# MCU.net
KiCad netlist of a schematic drawn in Altium Designer
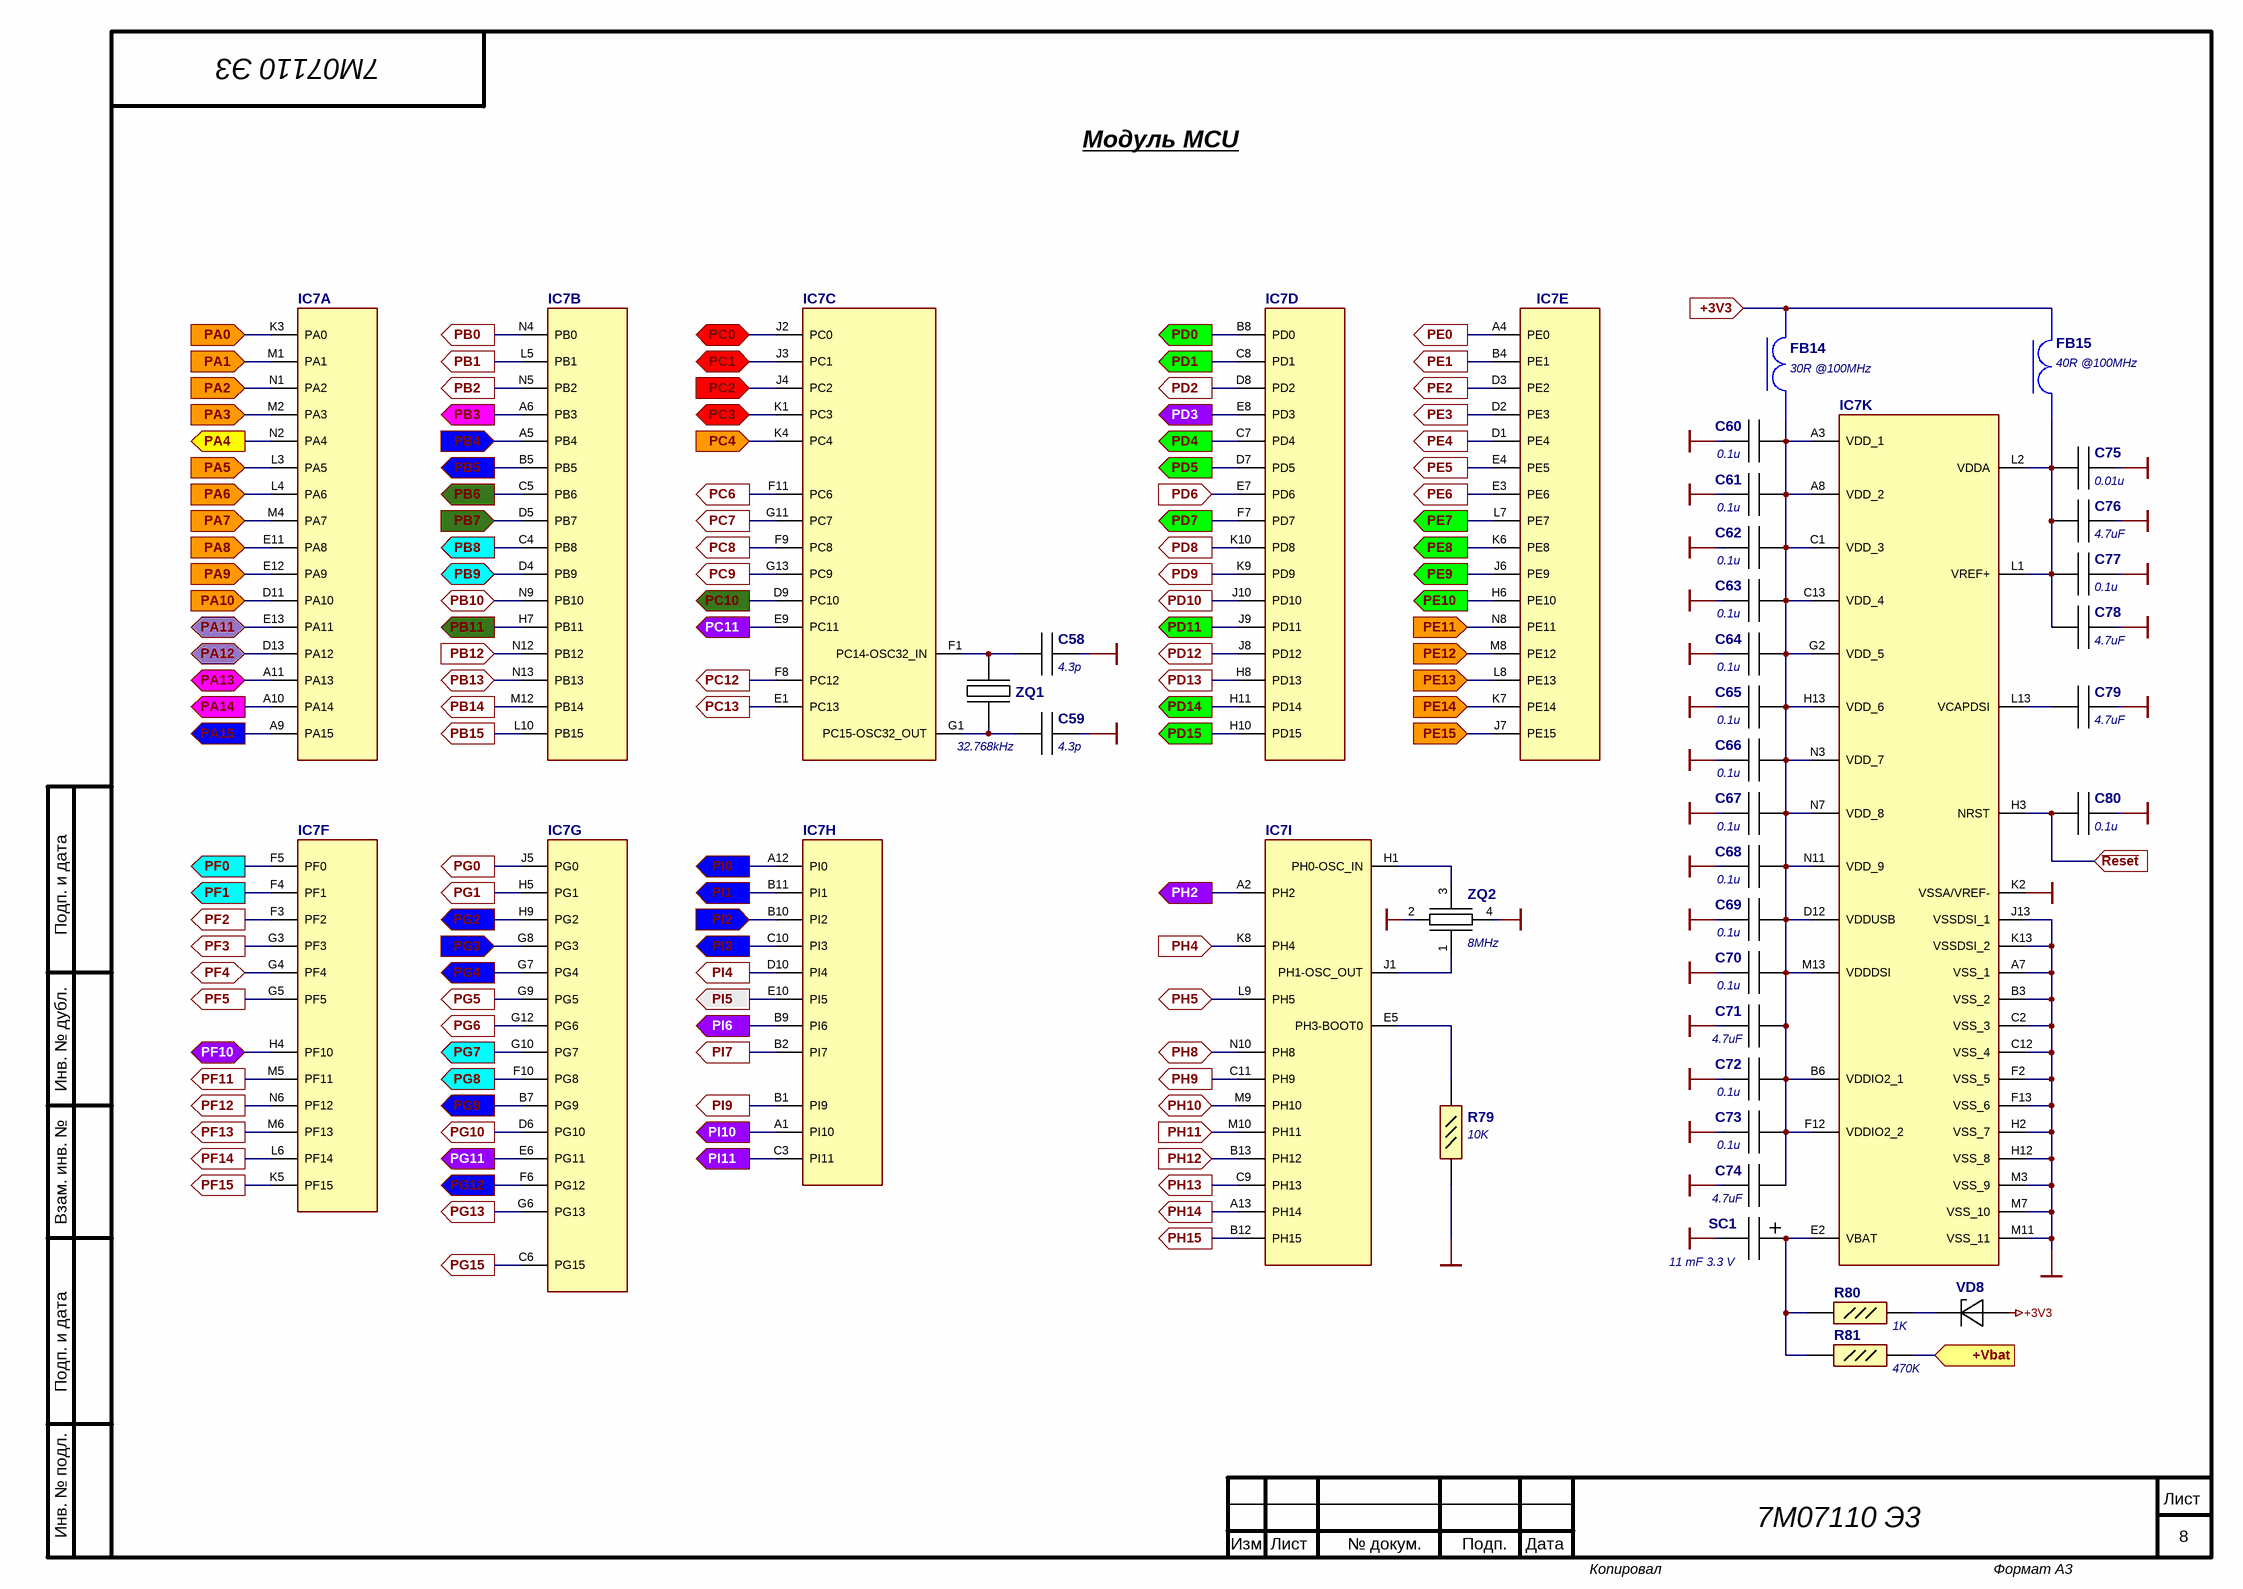
[diagram p0: Модуль MCU.SchDoc]

(export (version "E")
  (design (tool "Eeschema 10.0.6"))
  (components
    (comp (ref "C58")
      (value "4.3p")
      (footprint ":CAP0402 100x50x50")
      (description "CAP CER  50V C0G/NP0 0402")
      (fields (field (name "MANUFACTURER_PART_NUMBER") "GJM1555C1H4R3CB01D"))
      (libsource (lib "Capacitors 0402") (part "GJM1555C1H4R3CB01D"))
    )
    (comp (ref "C59")
      (value "4.3p")
      (footprint ":CAP0402 100x50x50")
      (description "CAP CER  50V C0G/NP0 0402")
      (fields (field (name "MANUFACTURER_PART_NUMBER") "GJM1555C1H4R3CB01D"))
      (libsource (lib "Capacitors 0402") (part "GJM1555C1H4R3CB01D"))
    )
    (comp (ref "C60")
      (value "0.1u")
      (footprint ":CAP0402 100x50x50")
      (description "±10% 25V Ceramic Capacitor X7R 0402 (1005 Metric)")
      (fields
        (field (name "MANUFACTURER_PART_NUMBER") "GRM155R71E104KE14J")
        (field (name "MOUSER PART NUMBER") "81-GRM155R71E104KE4J")
      )
      (libsource (lib "Capacitors 0402") (part "GRM155R71E104KE14J"))
    )
    (comp (ref "C61")
      (value "0.1u")
      (footprint ":CAP0402 100x50x50")
      (description "±10% 25V Ceramic Capacitor X7R 0402 (1005 Metric)")
      (fields
        (field (name "MANUFACTURER_PART_NUMBER") "GRM155R71E104KE14J")
        (field (name "MOUSER PART NUMBER") "81-GRM155R71E104KE4J")
      )
      (libsource (lib "Capacitors 0402") (part "GRM155R71E104KE14J"))
    )
    (comp (ref "C62")
      (value "0.1u")
      (footprint ":CAP0402 100x50x50")
      (description "±10% 25V Ceramic Capacitor X7R 0402 (1005 Metric)")
      (fields
        (field (name "MANUFACTURER_PART_NUMBER") "GRM155R71E104KE14J")
        (field (name "MOUSER PART NUMBER") "81-GRM155R71E104KE4J")
      )
      (libsource (lib "Capacitors 0402") (part "GRM155R71E104KE14J"))
    )
    (comp (ref "C63")
      (value "0.1u")
      (footprint ":CAP0402 100x50x50")
      (description "±10% 25V Ceramic Capacitor X7R 0402 (1005 Metric)")
      (fields
        (field (name "MANUFACTURER_PART_NUMBER") "GRM155R71E104KE14J")
        (field (name "MOUSER PART NUMBER") "81-GRM155R71E104KE4J")
      )
      (libsource (lib "Capacitors 0402") (part "GRM155R71E104KE14J"))
    )
    (comp (ref "C64")
      (value "0.1u")
      (footprint ":CAP0402 100x50x50")
      (description "±10% 25V Ceramic Capacitor X7R 0402 (1005 Metric)")
      (fields
        (field (name "MANUFACTURER_PART_NUMBER") "GRM155R71E104KE14J")
        (field (name "MOUSER PART NUMBER") "81-GRM155R71E104KE4J")
      )
      (libsource (lib "Capacitors 0402") (part "GRM155R71E104KE14J"))
    )
    (comp (ref "C65")
      (value "0.1u")
      (footprint ":CAP0402 100x50x50")
      (description "±10% 25V Ceramic Capacitor X7R 0402 (1005 Metric)")
      (fields
        (field (name "MANUFACTURER_PART_NUMBER") "GRM155R71E104KE14J")
        (field (name "MOUSER PART NUMBER") "81-GRM155R71E104KE4J")
      )
      (libsource (lib "Capacitors 0402") (part "GRM155R71E104KE14J"))
    )
    (comp (ref "C66")
      (value "0.1u")
      (footprint ":CAP0402 100x50x50")
      (description "±10% 25V Ceramic Capacitor X7R 0402 (1005 Metric)")
      (fields
        (field (name "MANUFACTURER_PART_NUMBER") "GRM155R71E104KE14J")
        (field (name "MOUSER PART NUMBER") "81-GRM155R71E104KE4J")
      )
      (libsource (lib "Capacitors 0402") (part "GRM155R71E104KE14J"))
    )
    (comp (ref "C67")
      (value "0.1u")
      (footprint ":CAP0402 100x50x50")
      (description "±10% 25V Ceramic Capacitor X7R 0402 (1005 Metric)")
      (fields
        (field (name "MANUFACTURER_PART_NUMBER") "GRM155R71E104KE14J")
        (field (name "MOUSER PART NUMBER") "81-GRM155R71E104KE4J")
      )
      (libsource (lib "Capacitors 0402") (part "GRM155R71E104KE14J"))
    )
    (comp (ref "C68")
      (value "0.1u")
      (footprint ":CAP0402 100x50x50")
      (description "±10% 25V Ceramic Capacitor X7R 0402 (1005 Metric)")
      (fields
        (field (name "MANUFACTURER_PART_NUMBER") "GRM155R71E104KE14J")
        (field (name "MOUSER PART NUMBER") "81-GRM155R71E104KE4J")
      )
      (libsource (lib "Capacitors 0402") (part "GRM155R71E104KE14J"))
    )
    (comp (ref "C69")
      (value "0.1u")
      (footprint ":CAP0402 100x50x50")
      (description "±10% 25V Ceramic Capacitor X7R 0402 (1005 Metric)")
      (fields
        (field (name "MANUFACTURER_PART_NUMBER") "GRM155R71E104KE14J")
        (field (name "MOUSER PART NUMBER") "81-GRM155R71E104KE4J")
      )
      (libsource (lib "Capacitors 0402") (part "GRM155R71E104KE14J"))
    )
    (comp (ref "C70")
      (value "0.1u")
      (footprint ":CAP0402 100x50x50")
      (description "±10% 25V Ceramic Capacitor X7R 0402 (1005 Metric)")
      (fields
        (field (name "MANUFACTURER_PART_NUMBER") "GRM155R71E104KE14J")
        (field (name "MOUSER PART NUMBER") "81-GRM155R71E104KE4J")
      )
      (libsource (lib "Capacitors 0402") (part "GRM155R71E104KE14J"))
    )
    (comp (ref "C71")
      (value "4.7uF")
      (footprint ":CAP0805 C2012X125")
      (description "CAP CER 4.7uF 25V X7R 0805")
      (fields (field (name "MANUFACTURER_PART_NUMBER") "GRM21BZ71E475KE15L"))
      (libsource (lib "Capacitors 0805") (part "GRM21BZ71E475KE15L"))
    )
    (comp (ref "C72")
      (value "0.1u")
      (footprint ":CAP0402 100x50x50")
      (description "±10% 25V Ceramic Capacitor X7R 0402 (1005 Metric)")
      (fields
        (field (name "MANUFACTURER_PART_NUMBER") "GRM155R71E104KE14J")
        (field (name "MOUSER PART NUMBER") "81-GRM155R71E104KE4J")
      )
      (libsource (lib "Capacitors 0402") (part "GRM155R71E104KE14J"))
    )
    (comp (ref "C73")
      (value "0.1u")
      (footprint ":CAP0402 100x50x50")
      (description "±10% 25V Ceramic Capacitor X7R 0402 (1005 Metric)")
      (fields
        (field (name "MANUFACTURER_PART_NUMBER") "GRM155R71E104KE14J")
        (field (name "MOUSER PART NUMBER") "81-GRM155R71E104KE4J")
      )
      (libsource (lib "Capacitors 0402") (part "GRM155R71E104KE14J"))
    )
    (comp (ref "C74")
      (value "4.7uF")
      (footprint ":CAP0805 C2012X125")
      (description "CAP CER 4.7uF 25V X7R 0805")
      (fields (field (name "MANUFACTURER_PART_NUMBER") "GRM21BZ71E475KE15L"))
      (libsource (lib "Capacitors 0805") (part "GRM21BZ71E475KE15L"))
    )
    (comp (ref "C75")
      (value "0.01u")
      (footprint ":CAP0402 100x50x50")
      (description "±5% 35V Ceramic Capacitor C0G, NP0 0402 (1005 Metric)")
      (fields (field (name "MANUFACTURER_PART_NUMBER") "GRM1555CYA103JE01D"))
      (libsource (lib "Capacitors 0402") (part "GRM1555CYA103JE01D"))
    )
    (comp (ref "C76")
      (value "4.7uF")
      (footprint ":CAP0805 C2012X125")
      (description "CAP CER 4.7uF 25V X7R 0805")
      (fields (field (name "MANUFACTURER_PART_NUMBER") "GRM21BZ71E475KE15L"))
      (libsource (lib "Capacitors 0805") (part "GRM21BZ71E475KE15L"))
    )
    (comp (ref "C77")
      (value "0.1u")
      (footprint ":CAP0402 100x50x50")
      (description "±10% 25V Ceramic Capacitor X7R 0402 (1005 Metric)")
      (fields
        (field (name "MANUFACTURER_PART_NUMBER") "GRM155R71E104KE14J")
        (field (name "MOUSER PART NUMBER") "81-GRM155R71E104KE4J")
      )
      (libsource (lib "Capacitors 0402") (part "GRM155R71E104KE14J"))
    )
    (comp (ref "C78")
      (value "4.7uF")
      (footprint ":CAP0805 C2012X125")
      (description "CAP CER 4.7uF 25V X7R 0805")
      (fields (field (name "MANUFACTURER_PART_NUMBER") "GRM21BZ71E475KE15L"))
      (libsource (lib "Capacitors 0805") (part "GRM21BZ71E475KE15L"))
    )
    (comp (ref "C79")
      (value "4.7uF")
      (footprint ":CAP0805 C2012X125")
      (description "CAP CER 4.7uF 25V X7R 0805")
      (fields (field (name "MANUFACTURER_PART_NUMBER") "GRM21BZ71E475KE15L"))
      (libsource (lib "Capacitors 0805") (part "GRM21BZ71E475KE15L"))
    )
    (comp (ref "C80")
      (value "0.1u")
      (footprint ":CAP0402 100x50x50")
      (description "±10% 25V Ceramic Capacitor X7R 0402 (1005 Metric)")
      (fields
        (field (name "MANUFACTURER_PART_NUMBER") "GRM155R71E104KE14J")
        (field (name "MOUSER PART NUMBER") "81-GRM155R71E104KE4J")
      )
      (libsource (lib "Capacitors 0402") (part "GRM155R71E104KE14J"))
    )
    (comp (ref "FB14")
      (value "30R @100MHz")
      (footprint ":FER BLM18SP300SN1D")
      (description "30 Ohms @ 100MHz 1 Power Line Ferrite Bead 0603 (1608 Metric) 6A 8mOhm")
      (fields
        (field (name "MANUFACTURER_PART_NUMBER") "BLM18SP300SN1D")
        (field (name "MOUSER PART NUMBER") "81-BLM18SP300SN1D")
      )
      (libsource (lib "Ferrite Bead") (part "BLM18SP300SN1D"))
    )
    (comp (ref "FB15")
      (value "40R @100MHz")
      (footprint ":FER MMZ1005Y400CTD25")
      (description "40 Ohms @ 100MHz 1 Signal Line Ferrite Bead 0402 (1005 Metric) 550mA 100mOhm")
      (fields
        (field (name "MANUFACTURER_PART_NUMBER") "MMZ1005Y400CTD25")
        (field (name "MOUSER PART NUMBER") "810-MMZ1005Y400CTD25")
      )
      (libsource (lib "Ferrite Bead") (part "MMZ1005Y400CTD25"))
    )
    (comp (ref "IC7")
      (value "STM32L4S9AII6")
      (footprint ":BGA169 P700X700X60")
      (description "MCU 32BIT 2MB FLASH")
      (fields (field (name "MOUSER PART NUMBER") "511-STM32L4S9AII6"))
      (libsource (lib "") (part "STM32L4S9AII6_1"))
    )
    (comp (ref "R79")
      (value "RC0402FR-07")
      (footprint ":RES0402")
      (fields (field (name "MANUFACTURER_PART_NUMBER (PART 2: VALUE)") "10K"))
      (libsource (lib "") (part "RC0402FR-07_1"))
    )
    (comp (ref "R80")
      (value "RC0402FR-07")
      (footprint ":RES0402")
      (fields (field (name "MANUFACTURER_PART_NUMBER (PART 2: VALUE)") "1K"))
      (libsource (lib "Resistors 0402") (part "RC0402FR-07"))
    )
    (comp (ref "R81")
      (value "RC0402FR-07")
      (footprint ":RES0402")
      (fields (field (name "MANUFACTURER_PART_NUMBER (PART 2: VALUE)") "470K"))
      (libsource (lib "Resistors 0402") (part "RC0402FR-07"))
    )
    (comp (ref "SC1")
      (value "11 mF 3.3 V")
      (footprint ":CAP CPH3225A")
      (description "11 mF (EDLC) Supercapacitor 3.3 V 1210 (3225 Metric)")
      (fields
        (field (name "MANUFACTURER_PART_NUMBER") "CPH3225A")
        (field (name "MOUSER PART NUMBER") "628-CPH3225A")
      )
      (libsource (lib "Super Capacitors") (part "CPH3225A"))
    )
    (comp (ref "VD8")
      (value "30V 0.1A")
      (footprint ":DIODE SOD-923F")
      (description "Diodes Schottky 0402 30V 0.1A")
      (fields
        (field (name "MANUFACTURER_PART_NUMBER") "CDBQR0130R")
        (field (name "MOUSER PART NUMBER") "750-CDBQR0130R")
      )
      (libsource (lib "Diodes 0402") (part "CDBQR0130R"))
    )
    (comp (ref "ZQ1")
      (value "32.768kHz")
      (footprint ":RESO 12.87181")
      (description "CRYSTAL 32.7680KHZ\r\n±20ppm Crystal 12.5pF 2-SMD\r\nESR: 70 kOhms")
      (fields (field (name "MANUFACTURER_PART_NUMBER") "12.87181"))
      (libsource (lib "Crystal and TXCO") (part "12.87181"))
    )
    (comp (ref "ZQ2")
      (value "8MHz")
      (footprint ":RESO LFXTAL069277REEL")
      (description "CRYSTAL 8MHz\r\n±20ppm Crystal 20pF 4-SMD\r\nESR: 150 Ohms")
      (fields (field (name "MANUFACTURER_PART_NUMBER") "LFXTAL069277REEL"))
      (libsource (lib "Crystal and TXCO") (part "LFXTAL069277REEL"))
    )
  )
  (nets
    (net (code "1") (name "+3V3") (class "Default")
      (node (ref "FB14") (pin "2") (pinfunction "2_2") (pintype "passive"))
      (node (ref "FB15") (pin "1") (pinfunction "1_1") (pintype "passive"))
      (node (ref "VD8") (pin "2") (pinfunction "A_2") (pintype "passive"))
    )
    (net (code "2") (name "/+Vbat") (class "Default")
      (node (ref "R81") (pin "1") (pinfunction "1_1") (pintype "passive"))
    )
    (net (code "3") (name "/PA0") (class "Default")
      (node (ref "IC7") (pin "K3") (pinfunction "PA0_K3") (pintype "passive"))
    )
    (net (code "4") (name "/PA1") (class "Default")
      (node (ref "IC7") (pin "M1") (pinfunction "PA1_M1") (pintype "passive"))
    )
    (net (code "5") (name "/PA2") (class "Default")
      (node (ref "IC7") (pin "N1") (pinfunction "PA2_N1") (pintype "passive"))
    )
    (net (code "6") (name "/PA3") (class "Default")
      (node (ref "IC7") (pin "M2") (pinfunction "PA3_M2") (pintype "passive"))
    )
    (net (code "7") (name "/PA4") (class "Default")
      (node (ref "IC7") (pin "N2") (pinfunction "PA4_N2") (pintype "passive"))
    )
    (net (code "8") (name "/PA5") (class "Default")
      (node (ref "IC7") (pin "L3") (pinfunction "PA5_L3") (pintype "passive"))
    )
    (net (code "9") (name "/PA6") (class "Default")
      (node (ref "IC7") (pin "L4") (pinfunction "PA6_L4") (pintype "passive"))
    )
    (net (code "10") (name "/PA7") (class "Default")
      (node (ref "IC7") (pin "M4") (pinfunction "PA7_M4") (pintype "passive"))
    )
    (net (code "11") (name "/PA8") (class "Default")
      (node (ref "IC7") (pin "E11") (pinfunction "PA8_E11") (pintype "passive"))
    )
    (net (code "12") (name "/PA9") (class "Default")
      (node (ref "IC7") (pin "E12") (pinfunction "PA9_E12") (pintype "passive"))
    )
    (net (code "13") (name "/PA10") (class "Default")
      (node (ref "IC7") (pin "D11") (pinfunction "PA10_D11") (pintype "passive"))
    )
    (net (code "14") (name "/PA11") (class "Default")
      (node (ref "IC7") (pin "E13") (pinfunction "PA11_E13") (pintype "passive"))
    )
    (net (code "15") (name "/PA12") (class "Default")
      (node (ref "IC7") (pin "D13") (pinfunction "PA12_D13") (pintype "passive"))
    )
    (net (code "16") (name "/PA13") (class "Default")
      (node (ref "IC7") (pin "A11") (pinfunction "PA13_A11") (pintype "passive"))
    )
    (net (code "17") (name "/PA14") (class "Default")
      (node (ref "IC7") (pin "A10") (pinfunction "PA14_A10") (pintype "passive"))
    )
    (net (code "18") (name "/PA15") (class "Default")
      (node (ref "IC7") (pin "A9") (pinfunction "PA15_A9") (pintype "passive"))
    )
    (net (code "19") (name "/PB0") (class "Default")
      (node (ref "IC7") (pin "N4") (pinfunction "PB0_N4") (pintype "passive"))
    )
    (net (code "20") (name "/PB1") (class "Default")
      (node (ref "IC7") (pin "L5") (pinfunction "PB1_L5") (pintype "passive"))
    )
    (net (code "21") (name "/PB2") (class "Default")
      (node (ref "IC7") (pin "N5") (pinfunction "PB2_N5") (pintype "passive"))
    )
    (net (code "22") (name "/PB3") (class "Default")
      (node (ref "IC7") (pin "A6") (pinfunction "PB3_A6") (pintype "passive"))
    )
    (net (code "23") (name "/PB4") (class "Default")
      (node (ref "IC7") (pin "A5") (pinfunction "PB4_A5") (pintype "passive"))
    )
    (net (code "24") (name "/PB5") (class "Default")
      (node (ref "IC7") (pin "B5") (pinfunction "PB5_B5") (pintype "passive"))
    )
    (net (code "25") (name "/PB6") (class "Default")
      (node (ref "IC7") (pin "C5") (pinfunction "PB6_C5") (pintype "passive"))
    )
    (net (code "26") (name "/PB7") (class "Default")
      (node (ref "IC7") (pin "D5") (pinfunction "PB7_D5") (pintype "passive"))
    )
    (net (code "27") (name "/PB8") (class "Default")
      (node (ref "IC7") (pin "C4") (pinfunction "PB8_C4") (pintype "passive"))
    )
    (net (code "28") (name "/PB9") (class "Default")
      (node (ref "IC7") (pin "D4") (pinfunction "PB9_D4") (pintype "passive"))
    )
    (net (code "29") (name "/PB10") (class "Default")
      (node (ref "IC7") (pin "N9") (pinfunction "PB10_N9") (pintype "passive"))
    )
    (net (code "30") (name "/PB11") (class "Default")
      (node (ref "IC7") (pin "H7") (pinfunction "PB11_H7") (pintype "passive"))
    )
    (net (code "31") (name "/PB12") (class "Default")
      (node (ref "IC7") (pin "N12") (pinfunction "PB12_N12") (pintype "passive"))
    )
    (net (code "32") (name "/PB13") (class "Default")
      (node (ref "IC7") (pin "N13") (pinfunction "PB13_N13") (pintype "passive"))
    )
    (net (code "33") (name "/PB14") (class "Default")
      (node (ref "IC7") (pin "M12") (pinfunction "PB14_M12") (pintype "passive"))
    )
    (net (code "34") (name "/PB15") (class "Default")
      (node (ref "IC7") (pin "L10") (pinfunction "PB15_L10") (pintype "passive"))
    )
    (net (code "35") (name "/PC0") (class "Default")
      (node (ref "IC7") (pin "J2") (pinfunction "PC0_J2") (pintype "passive"))
    )
    (net (code "36") (name "/PC1") (class "Default")
      (node (ref "IC7") (pin "J3") (pinfunction "PC1_J3") (pintype "passive"))
    )
    (net (code "37") (name "/PC2") (class "Default")
      (node (ref "IC7") (pin "J4") (pinfunction "PC2_J4") (pintype "passive"))
    )
    (net (code "38") (name "/PC3") (class "Default")
      (node (ref "IC7") (pin "K1") (pinfunction "PC3_K1") (pintype "passive"))
    )
    (net (code "39") (name "/PC4") (class "Default")
      (node (ref "IC7") (pin "K4") (pinfunction "PC4_K4") (pintype "passive"))
    )
    (net (code "40") (name "/PC6") (class "Default")
      (node (ref "IC7") (pin "F11") (pinfunction "PC6_F11") (pintype "passive"))
    )
    (net (code "41") (name "/PC7") (class "Default")
      (node (ref "IC7") (pin "G11") (pinfunction "PC7_G11") (pintype "passive"))
    )
    (net (code "42") (name "/PC8") (class "Default")
      (node (ref "IC7") (pin "F9") (pinfunction "PC8_F9") (pintype "passive"))
    )
    (net (code "43") (name "/PC9") (class "Default")
      (node (ref "IC7") (pin "G13") (pinfunction "PC9_G13") (pintype "passive"))
    )
    (net (code "44") (name "/PC10") (class "Default")
      (node (ref "IC7") (pin "D9") (pinfunction "PC10_D9") (pintype "passive"))
    )
    (net (code "45") (name "/PC11") (class "Default")
      (node (ref "IC7") (pin "E9") (pinfunction "PC11_E9") (pintype "passive"))
    )
    (net (code "46") (name "/PC12") (class "Default")
      (node (ref "IC7") (pin "F8") (pinfunction "PC12_F8") (pintype "passive"))
    )
    (net (code "47") (name "/PC13") (class "Default")
      (node (ref "IC7") (pin "E1") (pinfunction "PC13_E1") (pintype "passive"))
    )
    (net (code "48") (name "/PD0") (class "Default")
      (node (ref "IC7") (pin "B8") (pinfunction "PD0_B8") (pintype "passive"))
    )
    (net (code "49") (name "/PD1") (class "Default")
      (node (ref "IC7") (pin "C8") (pinfunction "PD1_C8") (pintype "passive"))
    )
    (net (code "50") (name "/PD2") (class "Default")
      (node (ref "IC7") (pin "D8") (pinfunction "PD2_D8") (pintype "passive"))
    )
    (net (code "51") (name "/PD3") (class "Default")
      (node (ref "IC7") (pin "E8") (pinfunction "PD3_E8") (pintype "passive"))
    )
    (net (code "52") (name "/PD4") (class "Default")
      (node (ref "IC7") (pin "C7") (pinfunction "PD4_C7") (pintype "passive"))
    )
    (net (code "53") (name "/PD5") (class "Default")
      (node (ref "IC7") (pin "D7") (pinfunction "PD5_D7") (pintype "passive"))
    )
    (net (code "54") (name "/PD6") (class "Default")
      (node (ref "IC7") (pin "E7") (pinfunction "PD6_E7") (pintype "passive"))
    )
    (net (code "55") (name "/PD7") (class "Default")
      (node (ref "IC7") (pin "F7") (pinfunction "PD7_F7") (pintype "passive"))
    )
    (net (code "56") (name "/PD8") (class "Default")
      (node (ref "IC7") (pin "K10") (pinfunction "PD8_K10") (pintype "passive"))
    )
    (net (code "57") (name "/PD9") (class "Default")
      (node (ref "IC7") (pin "K9") (pinfunction "PD9_K9") (pintype "passive"))
    )
    (net (code "58") (name "/PD10") (class "Default")
      (node (ref "IC7") (pin "J10") (pinfunction "PD10_J10") (pintype "passive"))
    )
    (net (code "59") (name "/PD11") (class "Default")
      (node (ref "IC7") (pin "J9") (pinfunction "PD11_J9") (pintype "passive"))
    )
    (net (code "60") (name "/PD12") (class "Default")
      (node (ref "IC7") (pin "J8") (pinfunction "PD12_J8") (pintype "passive"))
    )
    (net (code "61") (name "/PD13") (class "Default")
      (node (ref "IC7") (pin "H8") (pinfunction "PD13_H8") (pintype "passive"))
    )
    (net (code "62") (name "/PD14") (class "Default")
      (node (ref "IC7") (pin "H11") (pinfunction "PD14_H11") (pintype "passive"))
    )
    (net (code "63") (name "/PD15") (class "Default")
      (node (ref "IC7") (pin "H10") (pinfunction "PD15_H10") (pintype "passive"))
    )
    (net (code "64") (name "/PE0") (class "Default")
      (node (ref "IC7") (pin "A4") (pinfunction "PE0_A4") (pintype "passive"))
    )
    (net (code "65") (name "/PE1") (class "Default")
      (node (ref "IC7") (pin "B4") (pinfunction "PE1_B4") (pintype "passive"))
    )
    (net (code "66") (name "/PE2") (class "Default")
      (node (ref "IC7") (pin "D3") (pinfunction "PE2_D3") (pintype "passive"))
    )
    (net (code "67") (name "/PE3") (class "Default")
      (node (ref "IC7") (pin "D2") (pinfunction "PE3_D2") (pintype "passive"))
    )
    (net (code "68") (name "/PE4") (class "Default")
      (node (ref "IC7") (pin "D1") (pinfunction "PE4_D1") (pintype "passive"))
    )
    (net (code "69") (name "/PE5") (class "Default")
      (node (ref "IC7") (pin "E4") (pinfunction "PE5_E4") (pintype "passive"))
    )
    (net (code "70") (name "/PE6") (class "Default")
      (node (ref "IC7") (pin "E3") (pinfunction "PE6_E3") (pintype "passive"))
    )
    (net (code "71") (name "/PE7") (class "Default")
      (node (ref "IC7") (pin "L7") (pinfunction "PE7_L7") (pintype "passive"))
    )
    (net (code "72") (name "/PE8") (class "Default")
      (node (ref "IC7") (pin "K6") (pinfunction "PE8_K6") (pintype "passive"))
    )
    (net (code "73") (name "/PE9") (class "Default")
      (node (ref "IC7") (pin "J6") (pinfunction "PE9_J6") (pintype "passive"))
    )
    (net (code "74") (name "/PE10") (class "Default")
      (node (ref "IC7") (pin "H6") (pinfunction "PE10_H6") (pintype "passive"))
    )
    (net (code "75") (name "/PE11") (class "Default")
      (node (ref "IC7") (pin "N8") (pinfunction "PE11_N8") (pintype "passive"))
    )
    (net (code "76") (name "/PE12") (class "Default")
      (node (ref "IC7") (pin "M8") (pinfunction "PE12_M8") (pintype "passive"))
    )
    (net (code "77") (name "/PE13") (class "Default")
      (node (ref "IC7") (pin "L8") (pinfunction "PE13_L8") (pintype "passive"))
    )
    (net (code "78") (name "/PE14") (class "Default")
      (node (ref "IC7") (pin "K7") (pinfunction "PE14_K7") (pintype "passive"))
    )
    (net (code "79") (name "/PE15") (class "Default")
      (node (ref "IC7") (pin "J7") (pinfunction "PE15_J7") (pintype "passive"))
    )
    (net (code "80") (name "/PF0") (class "Default")
      (node (ref "IC7") (pin "F5") (pinfunction "PF0_F5") (pintype "passive"))
    )
    (net (code "81") (name "/PF1") (class "Default")
      (node (ref "IC7") (pin "F4") (pinfunction "PF1_F4") (pintype "passive"))
    )
    (net (code "82") (name "/PF2") (class "Default")
      (node (ref "IC7") (pin "F3") (pinfunction "PF2_F3") (pintype "passive"))
    )
    (net (code "83") (name "/PF3") (class "Default")
      (node (ref "IC7") (pin "G3") (pinfunction "PF3_G3") (pintype "passive"))
    )
    (net (code "84") (name "/PF4") (class "Default")
      (node (ref "IC7") (pin "G4") (pinfunction "PF4_G4") (pintype "passive"))
    )
    (net (code "85") (name "/PF5") (class "Default")
      (node (ref "IC7") (pin "G5") (pinfunction "PF5_G5") (pintype "passive"))
    )
    (net (code "86") (name "/PF10") (class "Default")
      (node (ref "IC7") (pin "H4") (pinfunction "PF10_H4") (pintype "passive"))
    )
    (net (code "87") (name "/PF11") (class "Default")
      (node (ref "IC7") (pin "M5") (pinfunction "PF11_M5") (pintype "passive"))
    )
    (net (code "88") (name "/PF12") (class "Default")
      (node (ref "IC7") (pin "N6") (pinfunction "PF12_N6") (pintype "passive"))
    )
    (net (code "89") (name "/PF13") (class "Default")
      (node (ref "IC7") (pin "M6") (pinfunction "PF13_M6") (pintype "passive"))
    )
    (net (code "90") (name "/PF14") (class "Default")
      (node (ref "IC7") (pin "L6") (pinfunction "PF14_L6") (pintype "passive"))
    )
    (net (code "91") (name "/PF15") (class "Default")
      (node (ref "IC7") (pin "K5") (pinfunction "PF15_K5") (pintype "passive"))
    )
    (net (code "92") (name "/PG0") (class "Default")
      (node (ref "IC7") (pin "J5") (pinfunction "PG0_J5") (pintype "passive"))
    )
    (net (code "93") (name "/PG1") (class "Default")
      (node (ref "IC7") (pin "H5") (pinfunction "PG1_H5") (pintype "passive"))
    )
    (net (code "94") (name "/PG2") (class "Default")
      (node (ref "IC7") (pin "H9") (pinfunction "PG2_H9") (pintype "passive"))
    )
    (net (code "95") (name "/PG3") (class "Default")
      (node (ref "IC7") (pin "G8") (pinfunction "PG3_G8") (pintype "passive"))
    )
    (net (code "96") (name "/PG4") (class "Default")
      (node (ref "IC7") (pin "G7") (pinfunction "PG4_G7") (pintype "passive"))
    )
    (net (code "97") (name "/PG5") (class "Default")
      (node (ref "IC7") (pin "G9") (pinfunction "PG5_G9") (pintype "passive"))
    )
    (net (code "98") (name "/PG6") (class "Default")
      (node (ref "IC7") (pin "G12") (pinfunction "PG6_G12") (pintype "passive"))
    )
    (net (code "99") (name "/PG7") (class "Default")
      (node (ref "IC7") (pin "G10") (pinfunction "PG7_G10") (pintype "passive"))
    )
    (net (code "100") (name "/PG8") (class "Default")
      (node (ref "IC7") (pin "F10") (pinfunction "PG8_F10") (pintype "passive"))
    )
    (net (code "101") (name "/PG9") (class "Default")
      (node (ref "IC7") (pin "B7") (pinfunction "PG9_B7") (pintype "passive"))
    )
    (net (code "102") (name "/PG10") (class "Default")
      (node (ref "IC7") (pin "D6") (pinfunction "PG10_D6") (pintype "passive"))
    )
    (net (code "103") (name "/PG11") (class "Default")
      (node (ref "IC7") (pin "E6") (pinfunction "PG11_E6") (pintype "passive"))
    )
    (net (code "104") (name "/PG12") (class "Default")
      (node (ref "IC7") (pin "F6") (pinfunction "PG12_F6") (pintype "passive"))
    )
    (net (code "105") (name "/PG13") (class "Default")
      (node (ref "IC7") (pin "G6") (pinfunction "PG13_G6") (pintype "passive"))
    )
    (net (code "106") (name "/PG15") (class "Default")
      (node (ref "IC7") (pin "C6") (pinfunction "PG15_C6") (pintype "passive"))
    )
    (net (code "107") (name "/PH2") (class "Default")
      (node (ref "IC7") (pin "A2") (pinfunction "PH2_A2") (pintype "passive"))
    )
    (net (code "108") (name "/PH4") (class "Default")
      (node (ref "IC7") (pin "K8") (pinfunction "PH4_K8") (pintype "passive"))
    )
    (net (code "109") (name "/PH5") (class "Default")
      (node (ref "IC7") (pin "L9") (pinfunction "PH5_L9") (pintype "passive"))
    )
    (net (code "110") (name "/PH8") (class "Default")
      (node (ref "IC7") (pin "N10") (pinfunction "PH8_N10") (pintype "passive"))
    )
    (net (code "111") (name "/PH9") (class "Default")
      (node (ref "IC7") (pin "C11") (pinfunction "PH9_C11") (pintype "passive"))
    )
    (net (code "112") (name "/PH10") (class "Default")
      (node (ref "IC7") (pin "M9") (pinfunction "PH10_M9") (pintype "passive"))
    )
    (net (code "113") (name "/PH11") (class "Default")
      (node (ref "IC7") (pin "M10") (pinfunction "PH11_M10") (pintype "passive"))
    )
    (net (code "114") (name "/PH12") (class "Default")
      (node (ref "IC7") (pin "B13") (pinfunction "PH12_B13") (pintype "passive"))
    )
    (net (code "115") (name "/PH13") (class "Default")
      (node (ref "IC7") (pin "C9") (pinfunction "PH13_C9") (pintype "passive"))
    )
    (net (code "116") (name "/PH14") (class "Default")
      (node (ref "IC7") (pin "A13") (pinfunction "PH14_A13") (pintype "passive"))
    )
    (net (code "117") (name "/PH15") (class "Default")
      (node (ref "IC7") (pin "B12") (pinfunction "PH15_B12") (pintype "passive"))
    )
    (net (code "118") (name "/PI0") (class "Default")
      (node (ref "IC7") (pin "A12") (pinfunction "PI0_A12") (pintype "passive"))
    )
    (net (code "119") (name "/PI1") (class "Default")
      (node (ref "IC7") (pin "B11") (pinfunction "PI1_B11") (pintype "passive"))
    )
    (net (code "120") (name "/PI2") (class "Default")
      (node (ref "IC7") (pin "B10") (pinfunction "PI2_B10") (pintype "passive"))
    )
    (net (code "121") (name "/PI3") (class "Default")
      (node (ref "IC7") (pin "C10") (pinfunction "PI3_C10") (pintype "passive"))
    )
    (net (code "122") (name "/PI4") (class "Default")
      (node (ref "IC7") (pin "D10") (pinfunction "PI4_D10") (pintype "passive"))
    )
    (net (code "123") (name "/PI5") (class "Default")
      (node (ref "IC7") (pin "E10") (pinfunction "PI5_E10") (pintype "passive"))
    )
    (net (code "124") (name "/PI6") (class "Default")
      (node (ref "IC7") (pin "B9") (pinfunction "PI6_B9") (pintype "passive"))
    )
    (net (code "125") (name "/PI7") (class "Default")
      (node (ref "IC7") (pin "B2") (pinfunction "PI7_B2") (pintype "passive"))
    )
    (net (code "126") (name "/PI9") (class "Default")
      (node (ref "IC7") (pin "B1") (pinfunction "PI9_B1") (pintype "passive"))
    )
    (net (code "127") (name "/PI10") (class "Default")
      (node (ref "IC7") (pin "A1") (pinfunction "PI10_A1") (pintype "passive"))
    )
    (net (code "128") (name "/PI11") (class "Default")
      (node (ref "IC7") (pin "C3") (pinfunction "PI11_C3") (pintype "passive"))
    )
    (net (code "129") (name "/~{Reset}") (class "Default")
      (node (ref "C80") (pin "1") (pinfunction "1_1") (pintype "passive"))
      (node (ref "IC7") (pin "H3") (pinfunction "NRST_H3") (pintype "passive"))
    )
    (net (code "130") (name "GND") (class "Default")
      (node (ref "C58") (pin "2") (pinfunction "2_2") (pintype "passive"))
      (node (ref "C59") (pin "2") (pinfunction "2_2") (pintype "passive"))
      (node (ref "C60") (pin "1") (pinfunction "1_1") (pintype "passive"))
      (node (ref "C61") (pin "1") (pinfunction "1_1") (pintype "passive"))
      (node (ref "C62") (pin "1") (pinfunction "1_1") (pintype "passive"))
      (node (ref "C63") (pin "1") (pinfunction "1_1") (pintype "passive"))
      (node (ref "C64") (pin "1") (pinfunction "1_1") (pintype "passive"))
      (node (ref "C65") (pin "1") (pinfunction "1_1") (pintype "passive"))
      (node (ref "C66") (pin "1") (pinfunction "1_1") (pintype "passive"))
      (node (ref "C67") (pin "1") (pinfunction "1_1") (pintype "passive"))
      (node (ref "C68") (pin "1") (pinfunction "1_1") (pintype "passive"))
      (node (ref "C69") (pin "1") (pinfunction "1_1") (pintype "passive"))
      (node (ref "C70") (pin "1") (pinfunction "1_1") (pintype "passive"))
      (node (ref "C71") (pin "2") (pinfunction "2_2") (pintype "passive"))
      (node (ref "C72") (pin "1") (pinfunction "1_1") (pintype "passive"))
      (node (ref "C73") (pin "1") (pinfunction "1_1") (pintype "passive"))
      (node (ref "C74") (pin "2") (pinfunction "2_2") (pintype "passive"))
      (node (ref "C75") (pin "2") (pinfunction "2_2") (pintype "passive"))
      (node (ref "C76") (pin "2") (pinfunction "2_2") (pintype "passive"))
      (node (ref "C77") (pin "2") (pinfunction "2_2") (pintype "passive"))
      (node (ref "C78") (pin "2") (pinfunction "2_2") (pintype "passive"))
      (node (ref "C79") (pin "2") (pinfunction "2_2") (pintype "passive"))
      (node (ref "C80") (pin "2") (pinfunction "2_2") (pintype "passive"))
      (node (ref "IC7") (pin "A7") (pinfunction "VSS_1_A7") (pintype "passive"))
      (node (ref "IC7") (pin "B3") (pinfunction "VSS_2_B3") (pintype "passive"))
      (node (ref "IC7") (pin "C12") (pinfunction "VSS_4_C12") (pintype "passive"))
      (node (ref "IC7") (pin "C2") (pinfunction "VSS_3_C2") (pintype "passive"))
      (node (ref "IC7") (pin "F13") (pinfunction "VSS_6_F13") (pintype "passive"))
      (node (ref "IC7") (pin "F2") (pinfunction "VSS_5_F2") (pintype "passive"))
      (node (ref "IC7") (pin "H12") (pinfunction "VSS_8_H12") (pintype "passive"))
      (node (ref "IC7") (pin "H2") (pinfunction "VSS_7_H2") (pintype "passive"))
      (node (ref "IC7") (pin "J13") (pinfunction "VSSDSI_1_J13") (pintype "passive"))
      (node (ref "IC7") (pin "K13") (pinfunction "VSSDSI_2_K13") (pintype "passive"))
      (node (ref "IC7") (pin "K2") (pinfunction "VSSA/VREF-_K2") (pintype "passive"))
      (node (ref "IC7") (pin "M11") (pinfunction "VSS_11_M11") (pintype "passive"))
      (node (ref "IC7") (pin "M3") (pinfunction "VSS_9_M3") (pintype "passive"))
      (node (ref "IC7") (pin "M7") (pinfunction "VSS_10_M7") (pintype "passive"))
      (node (ref "R79") (pin "1") (pinfunction "1_1") (pintype "passive"))
      (node (ref "SC1") (pin "2") (pinfunction "-_2") (pintype "passive"))
      (node (ref "ZQ2") (pin "2") (pinfunction "2_2") (pintype "passive"))
      (node (ref "ZQ2") (pin "4") (pinfunction "4_4") (pintype "passive"))
    )
    (net (code "131") (name "Net-(IC7C-PC14-OSC32_IN)") (class "Default")
      (node (ref "C58") (pin "1") (pinfunction "1_1") (pintype "passive"))
      (node (ref "IC7") (pin "F1") (pinfunction "PC14-OSC32_IN_F1") (pintype "passive"))
      (node (ref "ZQ1") (pin "2") (pinfunction "2_2") (pintype "passive"))
    )
    (net (code "132") (name "Net-(IC7C-PC15-OSC32_OUT)") (class "Default")
      (node (ref "C59") (pin "1") (pinfunction "1_1") (pintype "passive"))
      (node (ref "IC7") (pin "G1") (pinfunction "PC15-OSC32_OUT_G1") (pintype "passive"))
      (node (ref "ZQ1") (pin "1") (pinfunction "1_1") (pintype "passive"))
    )
    (net (code "133") (name "Net-(IC7I-PH0-OSC_IN)") (class "Default")
      (node (ref "IC7") (pin "H1") (pinfunction "PH0-OSC_IN_H1") (pintype "passive"))
      (node (ref "ZQ2") (pin "3") (pinfunction "3_3") (pintype "passive"))
    )
    (net (code "134") (name "Net-(IC7I-PH1-OSC_OUT)") (class "Default")
      (node (ref "IC7") (pin "J1") (pinfunction "PH1-OSC_OUT_J1") (pintype "passive"))
      (node (ref "ZQ2") (pin "1") (pinfunction "1_1") (pintype "passive"))
    )
    (net (code "135") (name "Net-(IC7I-PH3-BOOT0)") (class "Default")
      (node (ref "IC7") (pin "E5") (pinfunction "PH3-BOOT0_E5") (pintype "passive"))
      (node (ref "R79") (pin "2") (pinfunction "2_2") (pintype "passive"))
    )
    (net (code "136") (name "Net-(IC7K-VBAT)") (class "Default")
      (node (ref "IC7") (pin "E2") (pinfunction "VBAT_E2") (pintype "passive"))
      (node (ref "R80") (pin "2") (pinfunction "2_2") (pintype "passive"))
      (node (ref "R81") (pin "2") (pinfunction "2_2") (pintype "passive"))
      (node (ref "SC1") (pin "1") (pinfunction "+_1") (pintype "passive"))
    )
    (net (code "137") (name "Net-(IC7K-VCAPDSI)") (class "Default")
      (node (ref "C79") (pin "1") (pinfunction "1_1") (pintype "passive"))
      (node (ref "IC7") (pin "L13") (pinfunction "VCAPDSI_L13") (pintype "passive"))
    )
    (net (code "138") (name "Net-(IC7K-VDDA)") (class "Default")
      (node (ref "C75") (pin "1") (pinfunction "1_1") (pintype "passive"))
      (node (ref "C76") (pin "1") (pinfunction "1_1") (pintype "passive"))
      (node (ref "C77") (pin "1") (pinfunction "1_1") (pintype "passive"))
      (node (ref "C78") (pin "1") (pinfunction "1_1") (pintype "passive"))
      (node (ref "FB15") (pin "2") (pinfunction "2_2") (pintype "passive"))
      (node (ref "IC7") (pin "L1") (pinfunction "VREF+_L1") (pintype "passive"))
      (node (ref "IC7") (pin "L2") (pinfunction "VDDA_L2") (pintype "passive"))
    )
    (net (code "139") (name "Net-(IC7K-VDDDSI)") (class "Default")
      (node (ref "C60") (pin "2") (pinfunction "2_2") (pintype "passive"))
      (node (ref "C61") (pin "2") (pinfunction "2_2") (pintype "passive"))
      (node (ref "C62") (pin "2") (pinfunction "2_2") (pintype "passive"))
      (node (ref "C63") (pin "2") (pinfunction "2_2") (pintype "passive"))
      (node (ref "C64") (pin "2") (pinfunction "2_2") (pintype "passive"))
      (node (ref "C65") (pin "2") (pinfunction "2_2") (pintype "passive"))
      (node (ref "C66") (pin "2") (pinfunction "2_2") (pintype "passive"))
      (node (ref "C67") (pin "2") (pinfunction "2_2") (pintype "passive"))
      (node (ref "C68") (pin "2") (pinfunction "2_2") (pintype "passive"))
      (node (ref "C69") (pin "2") (pinfunction "2_2") (pintype "passive"))
      (node (ref "C70") (pin "2") (pinfunction "2_2") (pintype "passive"))
      (node (ref "C71") (pin "1") (pinfunction "1_1") (pintype "passive"))
      (node (ref "C72") (pin "2") (pinfunction "2_2") (pintype "passive"))
      (node (ref "C73") (pin "2") (pinfunction "2_2") (pintype "passive"))
      (node (ref "C74") (pin "1") (pinfunction "1_1") (pintype "passive"))
      (node (ref "FB14") (pin "1") (pinfunction "1_1") (pintype "passive"))
      (node (ref "IC7") (pin "A3") (pinfunction "VDD_1_A3") (pintype "passive"))
      (node (ref "IC7") (pin "A8") (pinfunction "VDD_2_A8") (pintype "passive"))
      (node (ref "IC7") (pin "B6") (pinfunction "VDDIO2_1_B6") (pintype "passive"))
      (node (ref "IC7") (pin "C1") (pinfunction "VDD_3_C1") (pintype "passive"))
      (node (ref "IC7") (pin "C13") (pinfunction "VDD_4_C13") (pintype "passive"))
      (node (ref "IC7") (pin "D12") (pinfunction "VDDUSB_D12") (pintype "passive"))
      (node (ref "IC7") (pin "F12") (pinfunction "VDDIO2_2_F12") (pintype "passive"))
      (node (ref "IC7") (pin "G2") (pinfunction "VDD_5_G2") (pintype "passive"))
      (node (ref "IC7") (pin "H13") (pinfunction "VDD_6_H13") (pintype "passive"))
      (node (ref "IC7") (pin "M13") (pinfunction "VDDDSI_M13") (pintype "passive"))
      (node (ref "IC7") (pin "N11") (pinfunction "VDD_9_N11") (pintype "passive"))
      (node (ref "IC7") (pin "N3") (pinfunction "VDD_7_N3") (pintype "passive"))
      (node (ref "IC7") (pin "N7") (pinfunction "VDD_8_N7") (pintype "passive"))
    )
    (net (code "140") (name "Net-(VD8-K)") (class "Default")
      (node (ref "R80") (pin "1") (pinfunction "1_1") (pintype "passive"))
      (node (ref "VD8") (pin "1") (pinfunction "K_1") (pintype "passive"))
    )
  )
)
